# ESP_LoRa_GSM.net
KiCad netlist of a schematic drawn in EAGLE
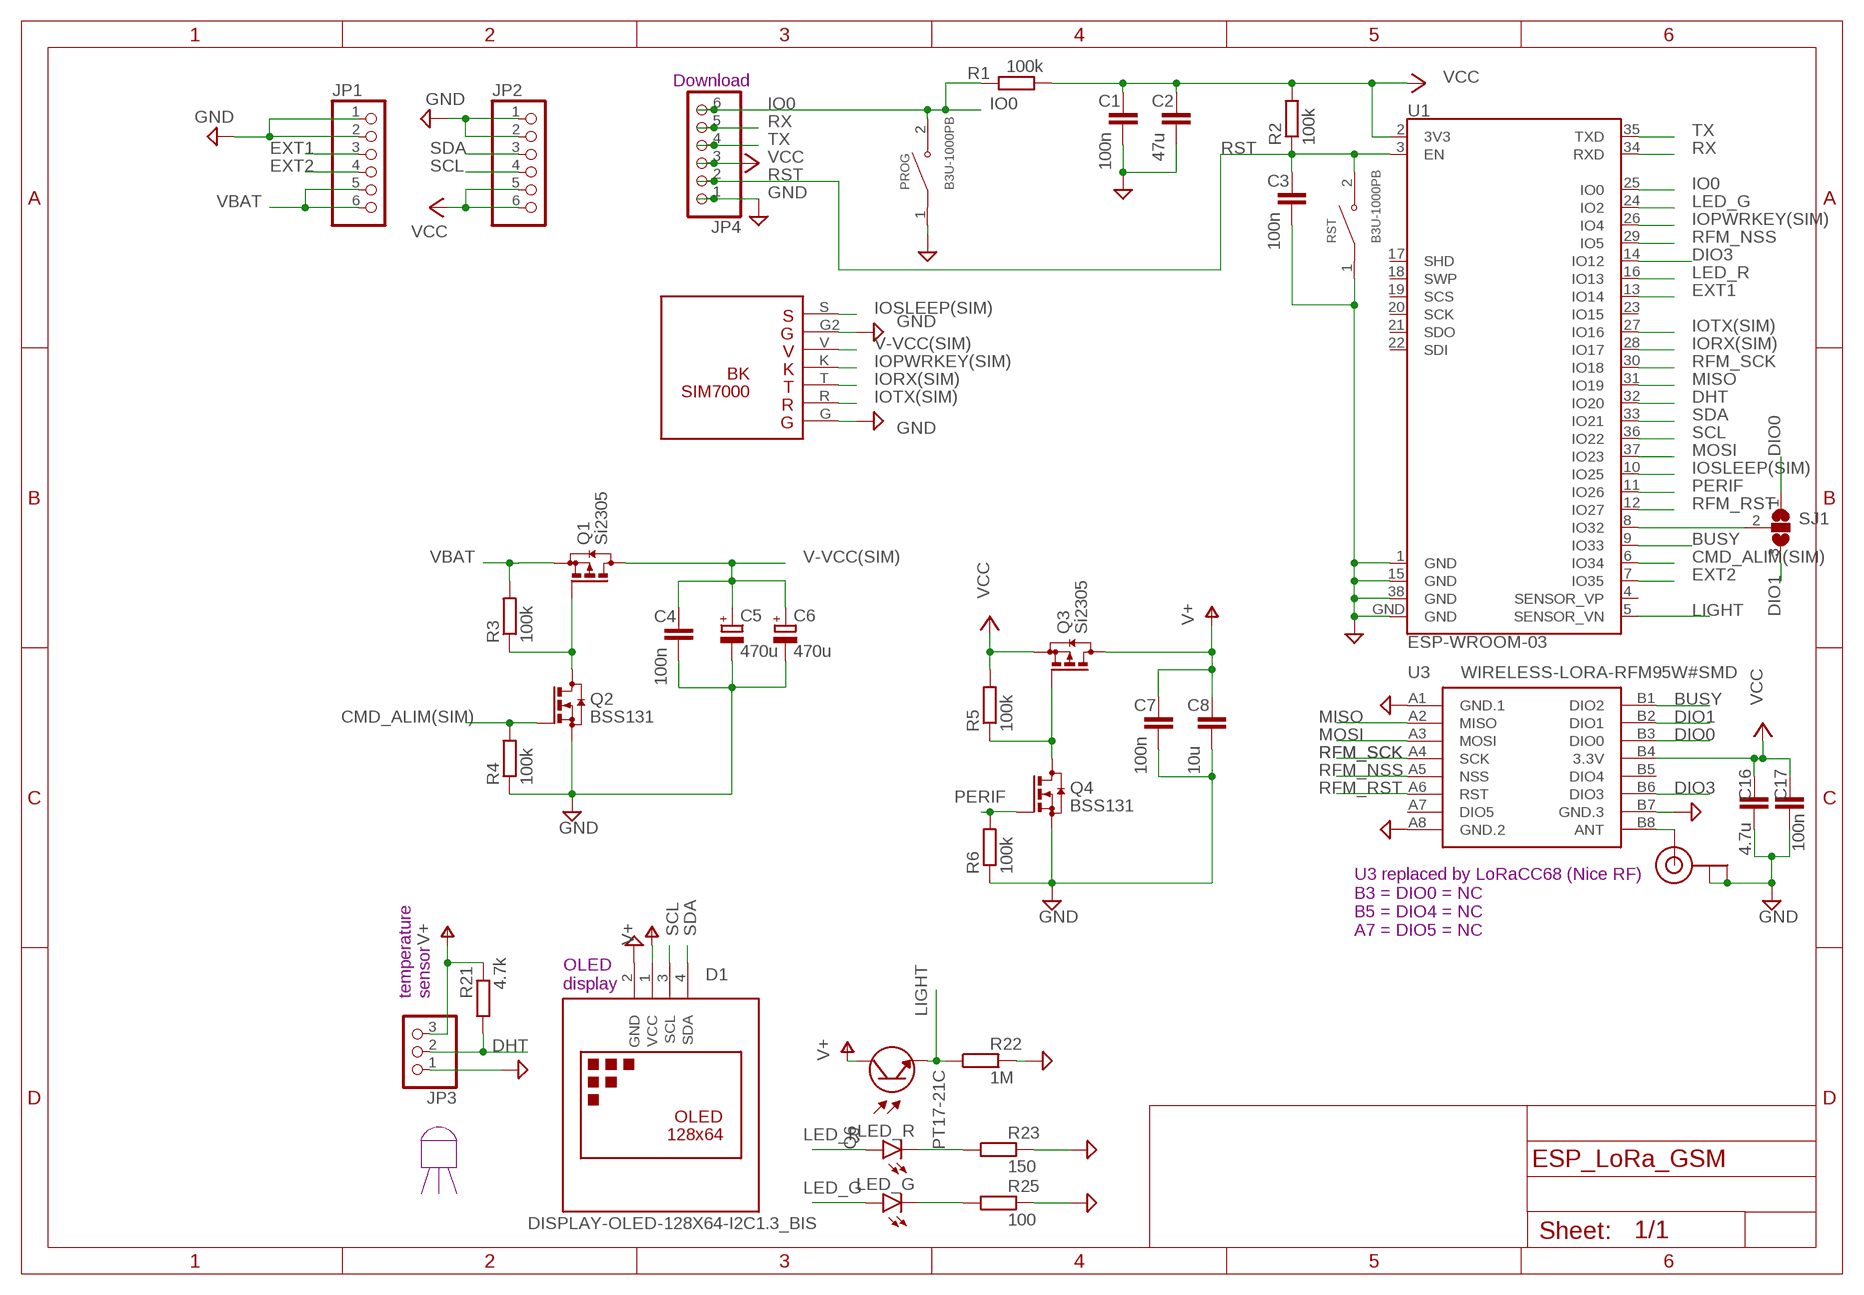
[diagram p0: schematic, sheet 1]

(export (version "E")
  (design (tool "Eeschema 10.0.6"))
  (components
    (comp (ref "C1")
      (value "100n")
      (footprint "eagle-import:C1206")
      (libsource (lib "eagle-import") (part "CC1206"))
    )
    (comp (ref "C2")
      (value "47u")
      (footprint "eagle-import:C0805")
      (libsource (lib "eagle-import") (part "C"))
    )
    (comp (ref "C3")
      (value "100n")
      (footprint "eagle-import:C1206")
      (libsource (lib "eagle-import") (part "CC1206"))
    )
    (comp (ref "C4")
      (value "100n")
      (footprint "eagle-import:C1206")
      (libsource (lib "eagle-import") (part "CC1206"))
    )
    (comp (ref "C5")
      (value "470u")
      (footprint "eagle-import:CT7343")
      (libsource (lib "eagle-import") (part "CPOL-EUCT7343"))
    )
    (comp (ref "C6")
      (value "470u")
      (footprint "eagle-import:CT7343")
      (libsource (lib "eagle-import") (part "CPOL-EUCT7343"))
    )
    (comp (ref "C7")
      (value "100n")
      (footprint "eagle-import:C1206")
      (libsource (lib "eagle-import") (part "CC1206"))
    )
    (comp (ref "C8")
      (value "10u")
      (footprint "eagle-import:C1206")
      (libsource (lib "eagle-import") (part "CC1206"))
    )
    (comp (ref "C16")
      (value "4.7u")
      (footprint "eagle-import:C1210")
      (libsource (lib "eagle-import") (part "CC1210"))
    )
    (comp (ref "C17")
      (value "100n")
      (footprint "eagle-import:C1206")
      (libsource (lib "eagle-import") (part "CC1206"))
    )
    (comp (ref "D1")
      (value "DISPLAY-OLED-128X64-I2C1.3_BIS")
      (footprint "eagle-import:DISPLAY-OLED-128X64-1.3-I2C_BIS")
      (libsource (lib "eagle-import") (part "DISPLAY-OLED-128X64-I2C1.3_BIS"))
    )
    (comp (ref "J1")
      (value "U.FL")
      (footprint "eagle-import:U.FL")
      (libsource (lib "eagle-import") (part "U.FL"))
    )
    (comp (ref "JP1")
      (value "PINHD-1X6S")
      (footprint "eagle-import:1X06S")
      (libsource (lib "eagle-import") (part "PINHD-1X6S"))
    )
    (comp (ref "JP2")
      (value "PINHD-1X6S")
      (footprint "eagle-import:1X06S")
      (libsource (lib "eagle-import") (part "PINHD-1X6S"))
    )
    (comp (ref "JP3")
      (value "PINHD-1X3")
      (footprint "eagle-import:1X03")
      (libsource (lib "eagle-import") (part "PINHD-1X3"))
    )
    (comp (ref "JP4")
      (value "PINHD-1X6S")
      (footprint "eagle-import:1X06S")
      (libsource (lib "eagle-import") (part "PINHD-1X6S"))
    )
    (comp (ref "LED_G")
      (value "LEDSMT1206")
      (footprint "eagle-import:1206")
      (libsource (lib "eagle-import") (part "LEDSMT1206"))
    )
    (comp (ref "LED_R")
      (value "LEDSMT1206")
      (footprint "eagle-import:1206")
      (libsource (lib "eagle-import") (part "LEDSMT1206"))
    )
    (comp (ref "PROG")
      (value "B3U-1000PB")
      (footprint "eagle-import:SW_B3U-1000PB")
      (libsource (lib "eagle-import") (part "B3U-1000PB"))
    )
    (comp (ref "Q1")
      (value "Si2305")
      (footprint "eagle-import:SOT23")
      (libsource (lib "eagle-import") (part "BSS84"))
    )
    (comp (ref "Q2")
      (value "BSS131")
      (footprint "eagle-import:SOT23")
      (libsource (lib "eagle-import") (part "BSS123"))
    )
    (comp (ref "Q3")
      (value "Si2305")
      (footprint "eagle-import:SOT23")
      (libsource (lib "eagle-import") (part "BSS84"))
    )
    (comp (ref "Q4")
      (value "BSS131")
      (footprint "eagle-import:SOT23")
      (libsource (lib "eagle-import") (part "BSS123"))
    )
    (comp (ref "Q6")
      (value "PT17-21C")
      (footprint "eagle-import:0805")
      (libsource (lib "eagle-import") (part "PT17-21C"))
    )
    (comp (ref "R1")
      (value "100k")
      (footprint "eagle-import:R1206")
      (libsource (lib "eagle-import") (part "RR1206"))
    )
    (comp (ref "R2")
      (value "100k")
      (footprint "eagle-import:R1206")
      (libsource (lib "eagle-import") (part "RR1206"))
    )
    (comp (ref "R3")
      (value "100k")
      (footprint "eagle-import:R1206")
      (libsource (lib "eagle-import") (part "RR1206"))
    )
    (comp (ref "R4")
      (value "100k")
      (footprint "eagle-import:R1206")
      (libsource (lib "eagle-import") (part "RR1206"))
    )
    (comp (ref "R5")
      (value "100k")
      (footprint "eagle-import:R1206")
      (libsource (lib "eagle-import") (part "RR1206"))
    )
    (comp (ref "R6")
      (value "100k")
      (footprint "eagle-import:R1206")
      (libsource (lib "eagle-import") (part "RR1206"))
    )
    (comp (ref "R21")
      (value "4.7k")
      (footprint "eagle-import:R1206")
      (libsource (lib "eagle-import") (part "RR1206"))
    )
    (comp (ref "R22")
      (value "1M")
      (footprint "eagle-import:R1206")
      (libsource (lib "eagle-import") (part "RR1206"))
    )
    (comp (ref "R23")
      (value "150")
      (footprint "eagle-import:R1206")
      (libsource (lib "eagle-import") (part "RR1206"))
    )
    (comp (ref "R25")
      (value "100")
      (footprint "eagle-import:R1206")
      (libsource (lib "eagle-import") (part "RR1206"))
    )
    (comp (ref "RST")
      (value "B3U-1000PB")
      (footprint "eagle-import:SW_B3U-1000PB")
      (libsource (lib "eagle-import") (part "B3U-1000PB"))
    )
    (comp (ref "SJ1")
      (value "SJ2W")
      (footprint "eagle-import:SJ_2")
      (libsource (lib "eagle-import") (part "SJ2W"))
    )
    (comp (ref "U1")
      (value "ESP-WROOM-03")
      (footprint "eagle-import:ESP-WROOM-03")
      (libsource (lib "eagle-import") (part "ESP-WROOM-03"))
    )
    (comp (ref "U2")
      (value "BK7000-V2")
      (footprint "eagle-import:SIM7000-BK")
      (libsource (lib "eagle-import") (part "BK7000-V2"))
    )
    (comp (ref "U3")
      (value "WIRELESS-LORA-RFM95W#SMD")
      (footprint "eagle-import:WIRELESS-LORA-RFM95W#SMD")
      (libsource (lib "eagle-import") (part "WIRELESS-LORA-RFM95W#SMD"))
    )
  )
  (nets
    (net (code "1") (name "/BUSY") (class "Default")
      (node (ref "U1") (pin "9") (pinfunction "IO33_9") (pintype "bidirectional"))
      (node (ref "U3") (pin "B1") (pinfunction "DIO2_B1") (pintype "bidirectional"))
    )
    (net (code "2") (name "/CMD_ALIM(SIM)") (class "Default")
      (node (ref "Q2") (pin "1") (pinfunction "G_1") (pintype "passive"))
      (node (ref "R4") (pin "2") (pinfunction "2_2") (pintype "passive"))
      (node (ref "U1") (pin "6") (pinfunction "IO34_6") (pintype "bidirectional"))
    )
    (net (code "3") (name "/DHT") (class "Default")
      (node (ref "JP3") (pin "2") (pinfunction "2_2") (pintype "passive"))
      (node (ref "R21") (pin "1") (pinfunction "1_1") (pintype "passive"))
      (node (ref "U1") (pin "32") (pinfunction "IO20_32") (pintype "bidirectional"))
    )
    (net (code "4") (name "/DIO0") (class "Default")
      (node (ref "SJ1") (pin "1") (pinfunction "1_1") (pintype "passive"))
      (node (ref "U3") (pin "B3") (pinfunction "DIO0_B3") (pintype "bidirectional"))
    )
    (net (code "5") (name "/DIO1") (class "Default")
      (node (ref "SJ1") (pin "3") (pinfunction "3_3") (pintype "passive"))
      (node (ref "U3") (pin "B2") (pinfunction "DIO1_B2") (pintype "bidirectional"))
    )
    (net (code "6") (name "/DIO3") (class "Default")
      (node (ref "U1") (pin "14") (pinfunction "IO12_14") (pintype "bidirectional"))
      (node (ref "U3") (pin "B6") (pinfunction "DIO3_B6") (pintype "bidirectional"))
    )
    (net (code "7") (name "/EXT1") (class "Default")
      (node (ref "JP1") (pin "3") (pinfunction "3_3") (pintype "passive"))
      (node (ref "U1") (pin "13") (pinfunction "IO14_13") (pintype "bidirectional"))
    )
    (net (code "8") (name "/EXT2") (class "Default")
      (node (ref "JP1") (pin "4") (pinfunction "4_4") (pintype "passive"))
      (node (ref "U1") (pin "7") (pinfunction "IO35_7") (pintype "bidirectional"))
    )
    (net (code "9") (name "/IO0") (class "Default")
      (node (ref "JP4") (pin "6") (pinfunction "6_6") (pintype "passive"))
      (node (ref "PROG") (pin "2") (pinfunction "2_2") (pintype "passive"))
      (node (ref "R1") (pin "2") (pinfunction "2_2") (pintype "passive"))
      (node (ref "U1") (pin "25") (pinfunction "IO0_25") (pintype "bidirectional"))
    )
    (net (code "10") (name "/IOPWRKEY(SIM)") (class "Default")
      (node (ref "U1") (pin "26") (pinfunction "IO4_26") (pintype "bidirectional"))
      (node (ref "U2") (pin "K") (pinfunction "K_K") (pintype "output"))
    )
    (net (code "11") (name "/IORX(SIM)") (class "Default")
      (node (ref "U1") (pin "28") (pinfunction "IO17_28") (pintype "bidirectional"))
      (node (ref "U2") (pin "T") (pinfunction "T_T") (pintype "output"))
    )
    (net (code "12") (name "/IOSLEEP(SIM)") (class "Default")
      (node (ref "U1") (pin "10") (pinfunction "IO25_10") (pintype "bidirectional"))
      (node (ref "U2") (pin "S") (pinfunction "S_S") (pintype "input"))
    )
    (net (code "13") (name "/IOTX(SIM)") (class "Default")
      (node (ref "U1") (pin "27") (pinfunction "IO16_27") (pintype "bidirectional"))
      (node (ref "U2") (pin "R") (pinfunction "R_R") (pintype "input"))
    )
    (net (code "14") (name "/LED_G") (class "Default")
      (node (ref "LED_G") (pin "A") (pinfunction "A_A") (pintype "passive"))
      (node (ref "U1") (pin "24") (pinfunction "IO2_24") (pintype "bidirectional"))
    )
    (net (code "15") (name "/LED_R") (class "Default")
      (node (ref "LED_R") (pin "A") (pinfunction "A_A") (pintype "passive"))
      (node (ref "U1") (pin "16") (pinfunction "IO13_16") (pintype "bidirectional"))
    )
    (net (code "16") (name "/LIGHT") (class "Default")
      (node (ref "Q6") (pin "1") (pinfunction "E_1") (pintype "passive"))
      (node (ref "R22") (pin "1") (pinfunction "1_1") (pintype "passive"))
      (node (ref "U1") (pin "5") (pinfunction "SENSOR_VN_5") (pintype "bidirectional"))
    )
    (net (code "17") (name "/MISO") (class "Default")
      (node (ref "U1") (pin "31") (pinfunction "IO19_31") (pintype "bidirectional"))
      (node (ref "U3") (pin "A2") (pinfunction "MISO_A2") (pintype "bidirectional"))
    )
    (net (code "18") (name "/MOSI") (class "Default")
      (node (ref "U1") (pin "37") (pinfunction "IO23_37") (pintype "bidirectional"))
      (node (ref "U3") (pin "A3") (pinfunction "MOSI_A3") (pintype "bidirectional"))
    )
    (net (code "19") (name "/PERIF") (class "Default")
      (node (ref "Q4") (pin "1") (pinfunction "G_1") (pintype "passive"))
      (node (ref "R6") (pin "2") (pinfunction "2_2") (pintype "passive"))
      (node (ref "U1") (pin "11") (pinfunction "IO26_11") (pintype "bidirectional"))
    )
    (net (code "20") (name "/RFM_NSS") (class "Default")
      (node (ref "U1") (pin "29") (pinfunction "IO5_29") (pintype "bidirectional"))
      (node (ref "U3") (pin "A5") (pinfunction "NSS_A5") (pintype "bidirectional"))
    )
    (net (code "21") (name "/RFM_RST") (class "Default")
      (node (ref "U1") (pin "12") (pinfunction "IO27_12") (pintype "bidirectional"))
      (node (ref "U3") (pin "A6") (pinfunction "RST_A6") (pintype "bidirectional"))
    )
    (net (code "22") (name "/RFM_SCK") (class "Default")
      (node (ref "U1") (pin "30") (pinfunction "IO18_30") (pintype "bidirectional"))
      (node (ref "U3") (pin "A4") (pinfunction "SCK_A4") (pintype "bidirectional"))
    )
    (net (code "23") (name "/RST") (class "Default")
      (node (ref "C3") (pin "1") (pinfunction "1_1") (pintype "passive"))
      (node (ref "JP4") (pin "2") (pinfunction "2_2") (pintype "passive"))
      (node (ref "R2") (pin "1") (pinfunction "1_1") (pintype "passive"))
      (node (ref "RST") (pin "2") (pinfunction "2_2") (pintype "passive"))
      (node (ref "U1") (pin "3") (pinfunction "EN_3") (pintype "bidirectional"))
    )
    (net (code "24") (name "/RX") (class "Default")
      (node (ref "JP4") (pin "5") (pinfunction "5_5") (pintype "passive"))
      (node (ref "U1") (pin "34") (pinfunction "RXD_34") (pintype "bidirectional"))
    )
    (net (code "25") (name "/SCL") (class "Default")
      (node (ref "D1") (pin "3") (pinfunction "SCL_3") (pintype "bidirectional"))
      (node (ref "JP2") (pin "4") (pinfunction "4_4") (pintype "passive"))
      (node (ref "U1") (pin "36") (pinfunction "IO22_36") (pintype "bidirectional"))
    )
    (net (code "26") (name "/SDA") (class "Default")
      (node (ref "D1") (pin "4") (pinfunction "SDA_4") (pintype "bidirectional"))
      (node (ref "JP2") (pin "3") (pinfunction "3_3") (pintype "passive"))
      (node (ref "U1") (pin "33") (pinfunction "IO21_33") (pintype "bidirectional"))
    )
    (net (code "27") (name "/TX") (class "Default")
      (node (ref "JP4") (pin "4") (pinfunction "4_4") (pintype "passive"))
      (node (ref "U1") (pin "35") (pinfunction "TXD_35") (pintype "bidirectional"))
    )
    (net (code "28") (name "/V-VCC(SIM)") (class "Default")
      (node (ref "C4") (pin "1") (pinfunction "1_1") (pintype "passive"))
      (node (ref "C5") (pin "+") (pinfunction "+_+") (pintype "passive"))
      (node (ref "C6") (pin "+") (pinfunction "+_+") (pintype "passive"))
      (node (ref "Q1") (pin "3") (pinfunction "D_3") (pintype "passive"))
      (node (ref "U2") (pin "V") (pinfunction "V_V") (pintype "power_in"))
    )
    (net (code "29") (name "/VBAT") (class "Default")
      (node (ref "JP1") (pin "5") (pinfunction "5_5") (pintype "passive"))
      (node (ref "JP1") (pin "6") (pinfunction "6_6") (pintype "passive"))
      (node (ref "Q1") (pin "2") (pinfunction "S_2") (pintype "passive"))
      (node (ref "R3") (pin "2") (pinfunction "2_2") (pintype "passive"))
    )
    (net (code "30") (name "GND") (class "Default")
      (node (ref "C1") (pin "2") (pinfunction "2_2") (pintype "passive"))
      (node (ref "C16") (pin "2") (pinfunction "2_2") (pintype "passive"))
      (node (ref "C17") (pin "2") (pinfunction "2_2") (pintype "passive"))
      (node (ref "C2") (pin "2") (pinfunction "2_2") (pintype "passive"))
      (node (ref "C3") (pin "2") (pinfunction "2_2") (pintype "passive"))
      (node (ref "C4") (pin "2") (pinfunction "2_2") (pintype "passive"))
      (node (ref "C5") (pin "-") (pinfunction "-_-") (pintype "passive"))
      (node (ref "C6") (pin "-") (pinfunction "-_-") (pintype "passive"))
      (node (ref "C7") (pin "2") (pinfunction "2_2") (pintype "passive"))
      (node (ref "C8") (pin "2") (pinfunction "2_2") (pintype "passive"))
      (node (ref "D1") (pin "2") (pinfunction "GND_2") (pintype "power_in"))
      (node (ref "J1") (pin "1") (pinfunction "GND_1") (pintype "passive"))
      (node (ref "J1") (pin "2") (pinfunction "GND_2") (pintype "passive"))
      (node (ref "JP1") (pin "1") (pinfunction "1_1") (pintype "passive"))
      (node (ref "JP1") (pin "2") (pinfunction "2_2") (pintype "passive"))
      (node (ref "JP2") (pin "1") (pinfunction "1_1") (pintype "passive"))
      (node (ref "JP2") (pin "2") (pinfunction "2_2") (pintype "passive"))
      (node (ref "JP3") (pin "1") (pinfunction "1_1") (pintype "passive"))
      (node (ref "JP4") (pin "1") (pinfunction "1_1") (pintype "passive"))
      (node (ref "PROG") (pin "1") (pinfunction "1_1") (pintype "passive"))
      (node (ref "Q2") (pin "2") (pinfunction "S_2") (pintype "passive"))
      (node (ref "Q4") (pin "2") (pinfunction "S_2") (pintype "passive"))
      (node (ref "R22") (pin "2") (pinfunction "2_2") (pintype "passive"))
      (node (ref "R23") (pin "2") (pinfunction "2_2") (pintype "passive"))
      (node (ref "R25") (pin "2") (pinfunction "2_2") (pintype "passive"))
      (node (ref "R4") (pin "1") (pinfunction "1_1") (pintype "passive"))
      (node (ref "R6") (pin "1") (pinfunction "1_1") (pintype "passive"))
      (node (ref "RST") (pin "1") (pinfunction "1_1") (pintype "passive"))
      (node (ref "U1") (pin "1") (pinfunction "GND_1") (pintype "bidirectional"))
      (node (ref "U1") (pin "15") (pinfunction "GND_15") (pintype "bidirectional"))
      (node (ref "U1") (pin "38") (pinfunction "GND_38") (pintype "bidirectional"))
      (node (ref "U1") (pin "GND") (pinfunction "GND_GND") (pintype "bidirectional"))
      (node (ref "U2") (pin "G") (pinfunction "G_G") (pintype "power_in"))
      (node (ref "U2") (pin "G2") (pinfunction "G2_G2") (pintype "power_in"))
      (node (ref "U3") (pin "A1") (pinfunction "GND.1_A1") (pintype "power_in"))
      (node (ref "U3") (pin "A8") (pinfunction "GND.2_A8") (pintype "power_in"))
      (node (ref "U3") (pin "B7") (pinfunction "GND.3_B7") (pintype "power_in"))
    )
    (net (code "31") (name "Net-(J1-SIGNAL)") (class "Default")
      (node (ref "J1") (pin "3") (pinfunction "SIGNAL_3") (pintype "passive"))
      (node (ref "U3") (pin "B8") (pinfunction "ANT_B8") (pintype "passive"))
    )
    (net (code "32") (name "Net-(LED_G-PadC)") (class "Default")
      (node (ref "LED_G") (pin "C") (pinfunction "C_C") (pintype "passive"))
      (node (ref "R25") (pin "1") (pinfunction "1_1") (pintype "passive"))
    )
    (net (code "33") (name "Net-(LED_R-PadC)") (class "Default")
      (node (ref "LED_R") (pin "C") (pinfunction "C_C") (pintype "passive"))
      (node (ref "R23") (pin "1") (pinfunction "1_1") (pintype "passive"))
    )
    (net (code "34") (name "Net-(Q1-G)") (class "Default")
      (node (ref "Q1") (pin "1") (pinfunction "G_1") (pintype "passive"))
      (node (ref "Q2") (pin "3") (pinfunction "D_3") (pintype "passive"))
      (node (ref "R3") (pin "1") (pinfunction "1_1") (pintype "passive"))
    )
    (net (code "35") (name "Net-(Q3-G)") (class "Default")
      (node (ref "Q3") (pin "1") (pinfunction "G_1") (pintype "passive"))
      (node (ref "Q4") (pin "3") (pinfunction "D_3") (pintype "passive"))
      (node (ref "R5") (pin "1") (pinfunction "1_1") (pintype "passive"))
    )
    (net (code "36") (name "Net-(U1-IO32)") (class "Default")
      (node (ref "SJ1") (pin "2") (pinfunction "2_2") (pintype "passive"))
      (node (ref "U1") (pin "8") (pinfunction "IO32_8") (pintype "bidirectional"))
    )
    (net (code "37") (name "V+") (class "Default")
      (node (ref "C7") (pin "1") (pinfunction "1_1") (pintype "passive"))
      (node (ref "C8") (pin "1") (pinfunction "1_1") (pintype "passive"))
      (node (ref "D1") (pin "1") (pinfunction "VCC_1") (pintype "power_in"))
      (node (ref "JP3") (pin "3") (pinfunction "3_3") (pintype "passive"))
      (node (ref "Q3") (pin "3") (pinfunction "D_3") (pintype "passive"))
      (node (ref "Q6") (pin "2") (pinfunction "C_2") (pintype "passive"))
      (node (ref "R21") (pin "2") (pinfunction "2_2") (pintype "passive"))
    )
    (net (code "38") (name "VCC") (class "Default")
      (node (ref "C1") (pin "1") (pinfunction "1_1") (pintype "passive"))
      (node (ref "C16") (pin "1") (pinfunction "1_1") (pintype "passive"))
      (node (ref "C17") (pin "1") (pinfunction "1_1") (pintype "passive"))
      (node (ref "C2") (pin "1") (pinfunction "1_1") (pintype "passive"))
      (node (ref "JP2") (pin "5") (pinfunction "5_5") (pintype "passive"))
      (node (ref "JP2") (pin "6") (pinfunction "6_6") (pintype "passive"))
      (node (ref "JP4") (pin "3") (pinfunction "3_3") (pintype "passive"))
      (node (ref "Q3") (pin "2") (pinfunction "S_2") (pintype "passive"))
      (node (ref "R1") (pin "1") (pinfunction "1_1") (pintype "passive"))
      (node (ref "R2") (pin "2") (pinfunction "2_2") (pintype "passive"))
      (node (ref "R5") (pin "2") (pinfunction "2_2") (pintype "passive"))
      (node (ref "U1") (pin "2") (pinfunction "3V3_2") (pintype "bidirectional"))
      (node (ref "U3") (pin "B4") (pinfunction "3.3V_B4") (pintype "power_in"))
    )
    (net (code "39") (name "unconnected-(U1-IO15-Pad23)") (class "Default")
      (node (ref "U1") (pin "23") (pinfunction "IO15_23") (pintype "bidirectional"))
    )
    (net (code "40") (name "unconnected-(U1-SCK-Pad20)") (class "Default")
      (node (ref "U1") (pin "20") (pinfunction "SCK_20") (pintype "bidirectional"))
    )
    (net (code "41") (name "unconnected-(U1-SCS-Pad19)") (class "Default")
      (node (ref "U1") (pin "19") (pinfunction "SCS_19") (pintype "bidirectional"))
    )
    (net (code "42") (name "unconnected-(U1-SDI-Pad22)") (class "Default")
      (node (ref "U1") (pin "22") (pinfunction "SDI_22") (pintype "bidirectional"))
    )
    (net (code "43") (name "unconnected-(U1-SDO-Pad21)") (class "Default")
      (node (ref "U1") (pin "21") (pinfunction "SDO_21") (pintype "bidirectional"))
    )
    (net (code "44") (name "unconnected-(U1-SENSOR_VP-Pad4)") (class "Default")
      (node (ref "U1") (pin "4") (pinfunction "SENSOR_VP_4") (pintype "bidirectional"))
    )
    (net (code "45") (name "unconnected-(U1-SHD-Pad17)") (class "Default")
      (node (ref "U1") (pin "17") (pinfunction "SHD_17") (pintype "bidirectional"))
    )
    (net (code "46") (name "unconnected-(U1-SWP-Pad18)") (class "Default")
      (node (ref "U1") (pin "18") (pinfunction "SWP_18") (pintype "bidirectional"))
    )
    (net (code "47") (name "unconnected-(U3-DIO4-PadB5)") (class "Default")
      (node (ref "U3") (pin "B5") (pinfunction "DIO4_B5") (pintype "bidirectional"))
    )
    (net (code "48") (name "unconnected-(U3-DIO5-PadA7)") (class "Default")
      (node (ref "U3") (pin "A7") (pinfunction "DIO5_A7") (pintype "bidirectional"))
    )
  )
)
